# ATSAMR21-Breakout.net
KiCad netlist of a schematic drawn in EAGLE
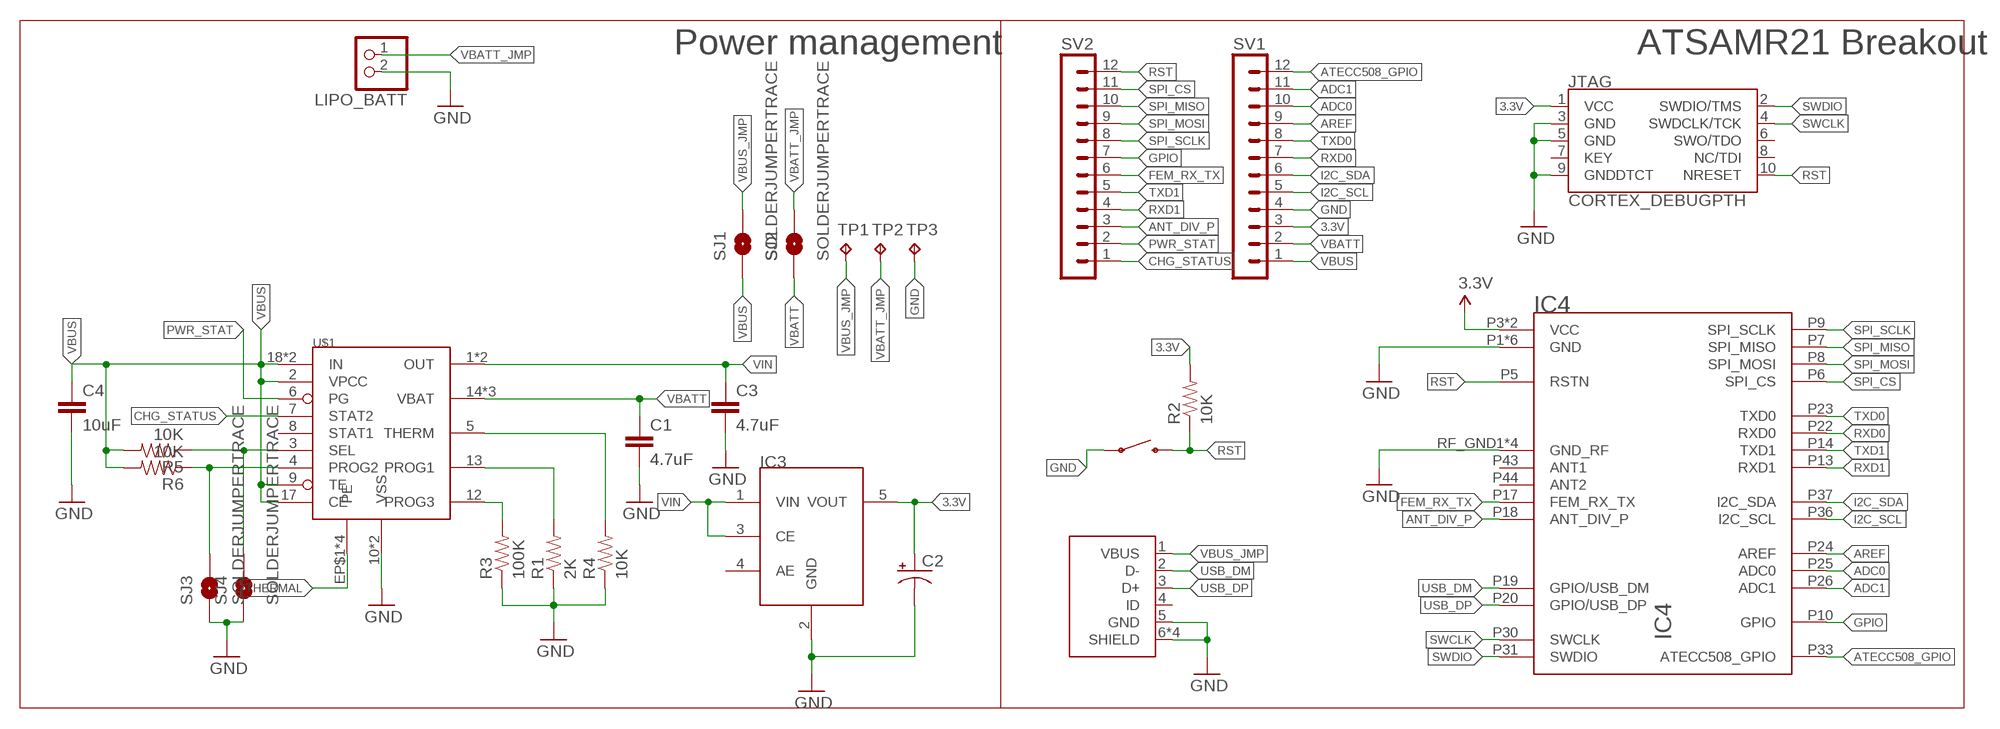
[diagram p0: schematic, sheet 1]

(export (version "E")
  (design (tool "Eeschema 10.0.6"))
  (components
    (comp (ref "C1")
      (value "4.7uF")
      (footprint "eagle-import:0805")
      (libsource (lib "eagle-import") (part "22UF-0805-6.3V-20%"))
    )
    (comp (ref "C2")
      (value "47uF")
      (footprint "eagle-import:1210-POLARIZED")
      (libsource (lib "eagle-import") (part "TPSB107M010R0400"))
    )
    (comp (ref "C3")
      (value "4.7uF")
      (footprint "eagle-import:0805")
      (libsource (lib "eagle-import") (part "22UF-0805-6.3V-20%"))
    )
    (comp (ref "C4")
      (value "10uF")
      (footprint "eagle-import:0805")
      (libsource (lib "eagle-import") (part "22UF-0805-6.3V-20%"))
    )
    (comp (ref "IC3")
      (value "NCP4589DSN33T1G")
      (footprint "eagle-import:SOT23-5")
      (libsource (lib "eagle-import") (part "NCP4589DSN33T1G"))
    )
    (comp (ref "IC4")
      (value "ATSAMR21G18-MR210UA")
      (footprint "eagle-import:ATSAMR21G18A-MR210UA")
      (libsource (lib "eagle-import") (part "ATSAMR21G18-MR210UA"))
    )
    (comp (ref "JTAG")
      (value "CORTEX_DEBUGPTH")
      (footprint "eagle-import:2X5-PTH-1.27MM")
      (libsource (lib "eagle-import") (part "CORTEX_DEBUGPTH"))
    )
    (comp (ref "LIPO_BATT")
      (value "JST_2PIN-THM-RA")
      (footprint "eagle-import:JST-PH-2-THM-RA")
      (libsource (lib "eagle-import") (part "JST_2PIN-THM-RA"))
    )
    (comp (ref "R1")
      (value "2K")
      (footprint "eagle-import:0805")
      (libsource (lib "eagle-import") (part "RESISTOR0805-RES"))
    )
    (comp (ref "R2")
      (value "10K")
      (footprint "eagle-import:0805")
      (libsource (lib "eagle-import") (part "RESISTOR0805-RES"))
    )
    (comp (ref "R3")
      (value "100K")
      (footprint "eagle-import:0805")
      (libsource (lib "eagle-import") (part "RESISTOR0805-RES"))
    )
    (comp (ref "R4")
      (value "10K")
      (footprint "eagle-import:0805")
      (libsource (lib "eagle-import") (part "RESISTOR0805-RES"))
    )
    (comp (ref "R5")
      (value "10K")
      (footprint "eagle-import:0805")
      (libsource (lib "eagle-import") (part "RESISTOR0805-RES"))
    )
    (comp (ref "R6")
      (value "10K")
      (footprint "eagle-import:0805")
      (libsource (lib "eagle-import") (part "RESISTOR0805-RES"))
    )
    (comp (ref "S1")
      (value "EVQ-PNF04M")
      (footprint "eagle-import:PANASONIC_EVQPE1_PN_5P")
      (libsource (lib "eagle-import") (part "EVQ-PNF04M"))
    )
    (comp (ref "SJ1")
      (value "SOLDERJUMPERTRACE")
      (footprint "eagle-import:SJ_2S-TRACE")
      (libsource (lib "eagle-import") (part "SOLDERJUMPERTRACE"))
    )
    (comp (ref "SJ2")
      (value "SOLDERJUMPERTRACE")
      (footprint "eagle-import:SJ_2S-TRACE")
      (libsource (lib "eagle-import") (part "SOLDERJUMPERTRACE"))
    )
    (comp (ref "SJ3")
      (value "SOLDERJUMPERTRACE")
      (footprint "eagle-import:SJ_2S-TRACE")
      (libsource (lib "eagle-import") (part "SOLDERJUMPERTRACE"))
    )
    (comp (ref "SJ4")
      (value "SOLDERJUMPERTRACE")
      (footprint "eagle-import:SJ_2S-TRACE")
      (libsource (lib "eagle-import") (part "SOLDERJUMPERTRACE"))
    )
    (comp (ref "SV1")
      (value "MA12-1")
      (footprint "eagle-import:MA12-1")
      (libsource (lib "eagle-import") (part "MA12-1"))
    )
    (comp (ref "SV2")
      (value "MA12-1")
      (footprint "eagle-import:MA12-1")
      (libsource (lib "eagle-import") (part "MA12-1"))
    )
    (comp (ref "TP1")
      (value "TPB2,54")
      (footprint "eagle-import:B2,54")
      (libsource (lib "eagle-import") (part "TPB2,54"))
    )
    (comp (ref "TP2")
      (value "TPB2,54")
      (footprint "eagle-import:B2,54")
      (libsource (lib "eagle-import") (part "TPB2,54"))
    )
    (comp (ref "TP3")
      (value "TPB2,54")
      (footprint "eagle-import:B2,54")
      (libsource (lib "eagle-import") (part "TPB2,54"))
    )
    (comp (ref "U$1")
      (value "MCP73871T")
      (footprint "eagle-import:QFN-20")
      (libsource (lib "eagle-import") (part "MCP73871T"))
    )
    (comp (ref "USB_CONN")
      (value "USB-MICRO-B")
      (footprint "eagle-import:HPL511")
      (libsource (lib "eagle-import") (part "USB-MICRO-B"))
    )
  )
  (nets
    (net (code "1") (name "/ID") (class "Default")
      (node (ref "USB_CONN") (pin "4") (pinfunction "ID_4") (pintype "power_in"))
    )
    (net (code "2") (name "3.3V") (class "Default")
      (node (ref "C2") (pin "1") (pinfunction "+_1") (pintype "passive"))
      (node (ref "IC3") (pin "5") (pinfunction "VOUT_5") (pintype "bidirectional"))
      (node (ref "IC4") (pin "P3") (pinfunction "VCC_P3") (pintype "power_in"))
      (node (ref "IC4") (pin "P4") (pinfunction "VCC_P4") (pintype "power_in"))
      (node (ref "JTAG") (pin "1") (pinfunction "VCC_1") (pintype "bidirectional"))
      (node (ref "R2") (pin "2") (pinfunction "2_2") (pintype "passive"))
      (node (ref "SV1") (pin "3") (pinfunction "3_3") (pintype "passive"))
    )
    (net (code "3") (name "ADC0") (class "Default")
      (node (ref "IC4") (pin "P25") (pinfunction "ADC0_P25") (pintype "bidirectional"))
      (node (ref "SV1") (pin "10") (pinfunction "10_10") (pintype "passive"))
    )
    (net (code "4") (name "ADC1") (class "Default")
      (node (ref "IC4") (pin "P26") (pinfunction "ADC1_P26") (pintype "bidirectional"))
      (node (ref "SV1") (pin "11") (pinfunction "11_11") (pintype "passive"))
    )
    (net (code "5") (name "ANT_DIV_P") (class "Default")
      (node (ref "IC4") (pin "P18") (pinfunction "ANT_DIV_P_P18") (pintype "bidirectional"))
      (node (ref "SV2") (pin "3") (pinfunction "3_3") (pintype "passive"))
    )
    (net (code "6") (name "AREF") (class "Default")
      (node (ref "IC4") (pin "P24") (pinfunction "AREF_P24") (pintype "power_in"))
      (node (ref "SV1") (pin "9") (pinfunction "9_9") (pintype "passive"))
    )
    (net (code "7") (name "ATECC508_GPIO") (class "Default")
      (node (ref "IC4") (pin "P33") (pinfunction "ATECC508_GPIO_P33") (pintype "bidirectional"))
      (node (ref "SV1") (pin "12") (pinfunction "12_12") (pintype "passive"))
    )
    (net (code "8") (name "CHG_STATUS") (class "Default")
      (node (ref "SV2") (pin "1") (pinfunction "1_1") (pintype "passive"))
      (node (ref "U$1") (pin "7") (pinfunction "STAT2_7") (pintype "output"))
    )
    (net (code "9") (name "FEM_RX_TX") (class "Default")
      (node (ref "IC4") (pin "P17") (pinfunction "FEM_RX_TX_P17") (pintype "bidirectional"))
      (node (ref "SV2") (pin "6") (pinfunction "6_6") (pintype "passive"))
    )
    (net (code "10") (name "GND") (class "Default")
      (node (ref "C1") (pin "2") (pinfunction "2_2") (pintype "passive"))
      (node (ref "C2") (pin "2") (pinfunction "-_2") (pintype "passive"))
      (node (ref "C3") (pin "2") (pinfunction "2_2") (pintype "passive"))
      (node (ref "C4") (pin "2") (pinfunction "2_2") (pintype "passive"))
      (node (ref "IC3") (pin "2") (pinfunction "GND_2") (pintype "bidirectional"))
      (node (ref "IC4") (pin "P1") (pinfunction "GND_P1") (pintype "power_in"))
      (node (ref "IC4") (pin "P12") (pinfunction "GND_P12") (pintype "power_in"))
      (node (ref "IC4") (pin "P2") (pinfunction "GND_P2") (pintype "power_in"))
      (node (ref "IC4") (pin "P29") (pinfunction "GND_P29") (pintype "power_in"))
      (node (ref "IC4") (pin "P41") (pinfunction "GND_P41") (pintype "power_in"))
      (node (ref "IC4") (pin "P42") (pinfunction "GND_P42") (pintype "power_in"))
      (node (ref "IC4") (pin "RF_GND1") (pinfunction "GND_RF_RF_GND1") (pintype "bidirectional"))
      (node (ref "IC4") (pin "RF_GND2") (pinfunction "GND_RF_RF_GND2") (pintype "bidirectional"))
      (node (ref "IC4") (pin "RF_GND3") (pinfunction "GND_RF_RF_GND3") (pintype "bidirectional"))
      (node (ref "IC4") (pin "RF_GND4") (pinfunction "GND_RF_RF_GND4") (pintype "bidirectional"))
      (node (ref "JTAG") (pin "3") (pinfunction "GND_3") (pintype "bidirectional"))
      (node (ref "JTAG") (pin "5") (pinfunction "GND_5") (pintype "bidirectional"))
      (node (ref "JTAG") (pin "9") (pinfunction "GNDDTCT_9") (pintype "bidirectional"))
      (node (ref "LIPO_BATT") (pin "2") (pinfunction "1_2") (pintype "passive"))
      (node (ref "R1") (pin "1") (pinfunction "1_1") (pintype "passive"))
      (node (ref "R3") (pin "1") (pinfunction "1_1") (pintype "passive"))
      (node (ref "R4") (pin "1") (pinfunction "1_1") (pintype "passive"))
      (node (ref "S1") (pin "P1") (pinfunction "1_P1") (pintype "bidirectional"))
      (node (ref "SJ3") (pin "1") (pinfunction "1_1") (pintype "passive"))
      (node (ref "SJ4") (pin "1") (pinfunction "1_1") (pintype "passive"))
      (node (ref "SV1") (pin "4") (pinfunction "4_4") (pintype "passive"))
      (node (ref "TP3") (pin "TP") (pinfunction "TP_TP") (pintype "input"))
      (node (ref "U$1") (pin "10") (pinfunction "VSS_10") (pintype "power_in"))
      (node (ref "U$1") (pin "11") (pinfunction "VSS_11") (pintype "power_in"))
      (node (ref "USB_CONN") (pin "5") (pinfunction "GND_5") (pintype "power_in"))
      (node (ref "USB_CONN") (pin "6") (pinfunction "SHIELD_6") (pintype "power_in"))
      (node (ref "USB_CONN") (pin "7") (pinfunction "SHIELD_7") (pintype "power_in"))
      (node (ref "USB_CONN") (pin "8") (pinfunction "SHIELD_8") (pintype "power_in"))
      (node (ref "USB_CONN") (pin "9") (pinfunction "SHIELD_9") (pintype "power_in"))
    )
    (net (code "11") (name "GPIO") (class "Default")
      (node (ref "IC4") (pin "P10") (pinfunction "GPIO_P10") (pintype "bidirectional"))
      (node (ref "SV2") (pin "7") (pinfunction "7_7") (pintype "passive"))
    )
    (net (code "12") (name "I2C_SCL") (class "Default")
      (node (ref "IC4") (pin "P36") (pinfunction "I2C_SCL_P36") (pintype "bidirectional"))
      (node (ref "SV1") (pin "5") (pinfunction "5_5") (pintype "passive"))
    )
    (net (code "13") (name "I2C_SDA") (class "Default")
      (node (ref "IC4") (pin "P37") (pinfunction "I2C_SDA_P37") (pintype "bidirectional"))
      (node (ref "SV1") (pin "6") (pinfunction "6_6") (pintype "passive"))
    )
    (net (code "14") (name "Net-(U$1-PROG1)") (class "Default")
      (node (ref "R1") (pin "2") (pinfunction "2_2") (pintype "passive"))
      (node (ref "U$1") (pin "13") (pinfunction "PROG1_13") (pintype "bidirectional"))
    )
    (net (code "15") (name "Net-(U$1-PROG2)") (class "Default")
      (node (ref "R6") (pin "1") (pinfunction "1_1") (pintype "passive"))
      (node (ref "SJ3") (pin "2") (pinfunction "2_2") (pintype "passive"))
      (node (ref "U$1") (pin "4") (pinfunction "PROG2_4") (pintype "input"))
    )
    (net (code "16") (name "Net-(U$1-PROG3)") (class "Default")
      (node (ref "R3") (pin "2") (pinfunction "2_2") (pintype "passive"))
      (node (ref "U$1") (pin "12") (pinfunction "PROG3_12") (pintype "bidirectional"))
    )
    (net (code "17") (name "Net-(U$1-SEL)") (class "Default")
      (node (ref "R5") (pin "1") (pinfunction "1_1") (pintype "passive"))
      (node (ref "SJ4") (pin "2") (pinfunction "2_2") (pintype "passive"))
      (node (ref "U$1") (pin "3") (pinfunction "SEL_3") (pintype "bidirectional"))
    )
    (net (code "18") (name "Net-(U$1-THERM)") (class "Default")
      (node (ref "R4") (pin "2") (pinfunction "2_2") (pintype "passive"))
      (node (ref "U$1") (pin "5") (pinfunction "THERM_5") (pintype "bidirectional"))
    )
    (net (code "19") (name "PWR_STAT") (class "Default")
      (node (ref "SV2") (pin "2") (pinfunction "2_2") (pintype "passive"))
      (node (ref "U$1") (pin "6") (pinfunction "PG_6") (pintype "output"))
    )
    (net (code "20") (name "RST") (class "Default")
      (node (ref "IC4") (pin "P5") (pinfunction "RSTN_P5") (pintype "input"))
      (node (ref "JTAG") (pin "10") (pinfunction "NRESET_10") (pintype "bidirectional"))
      (node (ref "R2") (pin "1") (pinfunction "1_1") (pintype "passive"))
      (node (ref "S1") (pin "P2") (pinfunction "2_P2") (pintype "bidirectional"))
      (node (ref "SV2") (pin "12") (pinfunction "12_12") (pintype "passive"))
    )
    (net (code "21") (name "RXD0") (class "Default")
      (node (ref "IC4") (pin "P22") (pinfunction "RXD0_P22") (pintype "bidirectional"))
      (node (ref "SV1") (pin "7") (pinfunction "7_7") (pintype "passive"))
    )
    (net (code "22") (name "RXD1") (class "Default")
      (node (ref "IC4") (pin "P13") (pinfunction "RXD1_P13") (pintype "bidirectional"))
      (node (ref "SV2") (pin "4") (pinfunction "4_4") (pintype "passive"))
    )
    (net (code "23") (name "SPI_CS") (class "Default")
      (node (ref "IC4") (pin "P6") (pinfunction "SPI_CS_P6") (pintype "bidirectional"))
      (node (ref "SV2") (pin "11") (pinfunction "11_11") (pintype "passive"))
    )
    (net (code "24") (name "SPI_MISO") (class "Default")
      (node (ref "IC4") (pin "P7") (pinfunction "SPI_MISO_P7") (pintype "bidirectional"))
      (node (ref "SV2") (pin "10") (pinfunction "10_10") (pintype "passive"))
    )
    (net (code "25") (name "SPI_MOSI") (class "Default")
      (node (ref "IC4") (pin "P8") (pinfunction "SPI_MOSI_P8") (pintype "bidirectional"))
      (node (ref "SV2") (pin "9") (pinfunction "9_9") (pintype "passive"))
    )
    (net (code "26") (name "SPI_SCLK") (class "Default")
      (node (ref "IC4") (pin "P9") (pinfunction "SPI_SCLK_P9") (pintype "bidirectional"))
      (node (ref "SV2") (pin "8") (pinfunction "8_8") (pintype "passive"))
    )
    (net (code "27") (name "SWCLK") (class "Default")
      (node (ref "IC4") (pin "P30") (pinfunction "SWCLK_P30") (pintype "bidirectional"))
      (node (ref "JTAG") (pin "4") (pinfunction "SWDCLK/TCK_4") (pintype "bidirectional"))
    )
    (net (code "28") (name "SWDIO") (class "Default")
      (node (ref "IC4") (pin "P31") (pinfunction "SWDIO_P31") (pintype "bidirectional"))
      (node (ref "JTAG") (pin "2") (pinfunction "SWDIO/TMS_2") (pintype "bidirectional"))
    )
    (net (code "29") (name "THERMAL") (class "Default")
      (node (ref "U$1") (pin "EP$1") (pinfunction "PE_EP$1") (pintype "bidirectional"))
      (node (ref "U$1") (pin "EP$2") (pinfunction "PE_EP$2") (pintype "bidirectional"))
      (node (ref "U$1") (pin "EP$3") (pinfunction "PE_EP$3") (pintype "bidirectional"))
      (node (ref "U$1") (pin "EP$4") (pinfunction "PE_EP$4") (pintype "bidirectional"))
    )
    (net (code "30") (name "TXD0") (class "Default")
      (node (ref "IC4") (pin "P23") (pinfunction "TXD0_P23") (pintype "bidirectional"))
      (node (ref "SV1") (pin "8") (pinfunction "8_8") (pintype "passive"))
    )
    (net (code "31") (name "TXD1") (class "Default")
      (node (ref "IC4") (pin "P14") (pinfunction "TXD1_P14") (pintype "bidirectional"))
      (node (ref "SV2") (pin "5") (pinfunction "5_5") (pintype "passive"))
    )
    (net (code "32") (name "USB_DM") (class "Default")
      (node (ref "IC4") (pin "P19") (pinfunction "GPIO/USB_DM_P19") (pintype "bidirectional"))
      (node (ref "USB_CONN") (pin "2") (pinfunction "D-_2") (pintype "power_in"))
    )
    (net (code "33") (name "USB_DP") (class "Default")
      (node (ref "IC4") (pin "P20") (pinfunction "GPIO/USB_DP_P20") (pintype "bidirectional"))
      (node (ref "USB_CONN") (pin "3") (pinfunction "D+_3") (pintype "power_in"))
    )
    (net (code "34") (name "VBATT") (class "Default")
      (node (ref "C1") (pin "1") (pinfunction "1_1") (pintype "passive"))
      (node (ref "SJ2") (pin "1") (pinfunction "1_1") (pintype "passive"))
      (node (ref "SV1") (pin "2") (pinfunction "2_2") (pintype "passive"))
      (node (ref "U$1") (pin "14") (pinfunction "VBAT_14") (pintype "bidirectional"))
      (node (ref "U$1") (pin "15") (pinfunction "VBAT_15") (pintype "bidirectional"))
      (node (ref "U$1") (pin "16") (pinfunction "VBAT_16") (pintype "bidirectional"))
    )
    (net (code "35") (name "VBATT_JMP") (class "Default")
      (node (ref "LIPO_BATT") (pin "1") (pinfunction "2_1") (pintype "passive"))
      (node (ref "SJ2") (pin "2") (pinfunction "2_2") (pintype "passive"))
      (node (ref "TP2") (pin "TP") (pinfunction "TP_TP") (pintype "input"))
    )
    (net (code "36") (name "VBUS") (class "Default")
      (node (ref "C4") (pin "1") (pinfunction "1_1") (pintype "passive"))
      (node (ref "R5") (pin "2") (pinfunction "2_2") (pintype "passive"))
      (node (ref "R6") (pin "2") (pinfunction "2_2") (pintype "passive"))
      (node (ref "SJ1") (pin "1") (pinfunction "1_1") (pintype "passive"))
      (node (ref "SV1") (pin "1") (pinfunction "1_1") (pintype "passive"))
      (node (ref "U$1") (pin "17") (pinfunction "CE_17") (pintype "input"))
      (node (ref "U$1") (pin "18") (pinfunction "IN_18") (pintype "power_in"))
      (node (ref "U$1") (pin "19") (pinfunction "IN_19") (pintype "power_in"))
      (node (ref "U$1") (pin "2") (pinfunction "VPCC_2") (pintype "bidirectional"))
      (node (ref "U$1") (pin "9") (pinfunction "TE_9") (pintype "input"))
    )
    (net (code "37") (name "VBUS_JMP") (class "Default")
      (node (ref "SJ1") (pin "2") (pinfunction "2_2") (pintype "passive"))
      (node (ref "TP1") (pin "TP") (pinfunction "TP_TP") (pintype "input"))
      (node (ref "USB_CONN") (pin "1") (pinfunction "VBUS_1") (pintype "power_in"))
    )
    (net (code "38") (name "VIN") (class "Default")
      (node (ref "C3") (pin "1") (pinfunction "1_1") (pintype "passive"))
      (node (ref "IC3") (pin "1") (pinfunction "VIN_1") (pintype "bidirectional"))
      (node (ref "IC3") (pin "3") (pinfunction "CE_3") (pintype "bidirectional"))
      (node (ref "U$1") (pin "1") (pinfunction "OUT_1") (pintype "power_in"))
      (node (ref "U$1") (pin "20") (pinfunction "OUT_20") (pintype "power_in"))
    )
    (net (code "39") (name "unconnected-(IC3-AE-Pad4)") (class "Default")
      (node (ref "IC3") (pin "4") (pinfunction "AE_4") (pintype "bidirectional"))
    )
    (net (code "40") (name "unconnected-(IC4-ANT1-PadP43)") (class "Default")
      (node (ref "IC4") (pin "P43") (pinfunction "ANT1_P43") (pintype "output"))
    )
    (net (code "41") (name "unconnected-(IC4-ANT2-PadP44)") (class "Default")
      (node (ref "IC4") (pin "P44") (pinfunction "ANT2_P44") (pintype "output"))
    )
    (net (code "42") (name "unconnected-(JTAG-KEY-Pad7)") (class "Default")
      (node (ref "JTAG") (pin "7") (pinfunction "KEY_7") (pintype "bidirectional"))
    )
    (net (code "43") (name "unconnected-(JTAG-NC{slash}TDI-Pad8)") (class "Default")
      (node (ref "JTAG") (pin "8") (pinfunction "NC/TDI_8") (pintype "bidirectional"))
    )
    (net (code "44") (name "unconnected-(JTAG-SWO{slash}TDO-Pad6)") (class "Default")
      (node (ref "JTAG") (pin "6") (pinfunction "SWO/TDO_6") (pintype "bidirectional"))
    )
    (net (code "45") (name "unconnected-(U$1-STAT1-Pad8)") (class "Default")
      (node (ref "U$1") (pin "8") (pinfunction "STAT1_8") (pintype "output"))
    )
  )
)
